# CRSC0002.net
KiCad netlist of a schematic drawn in Altium Designer
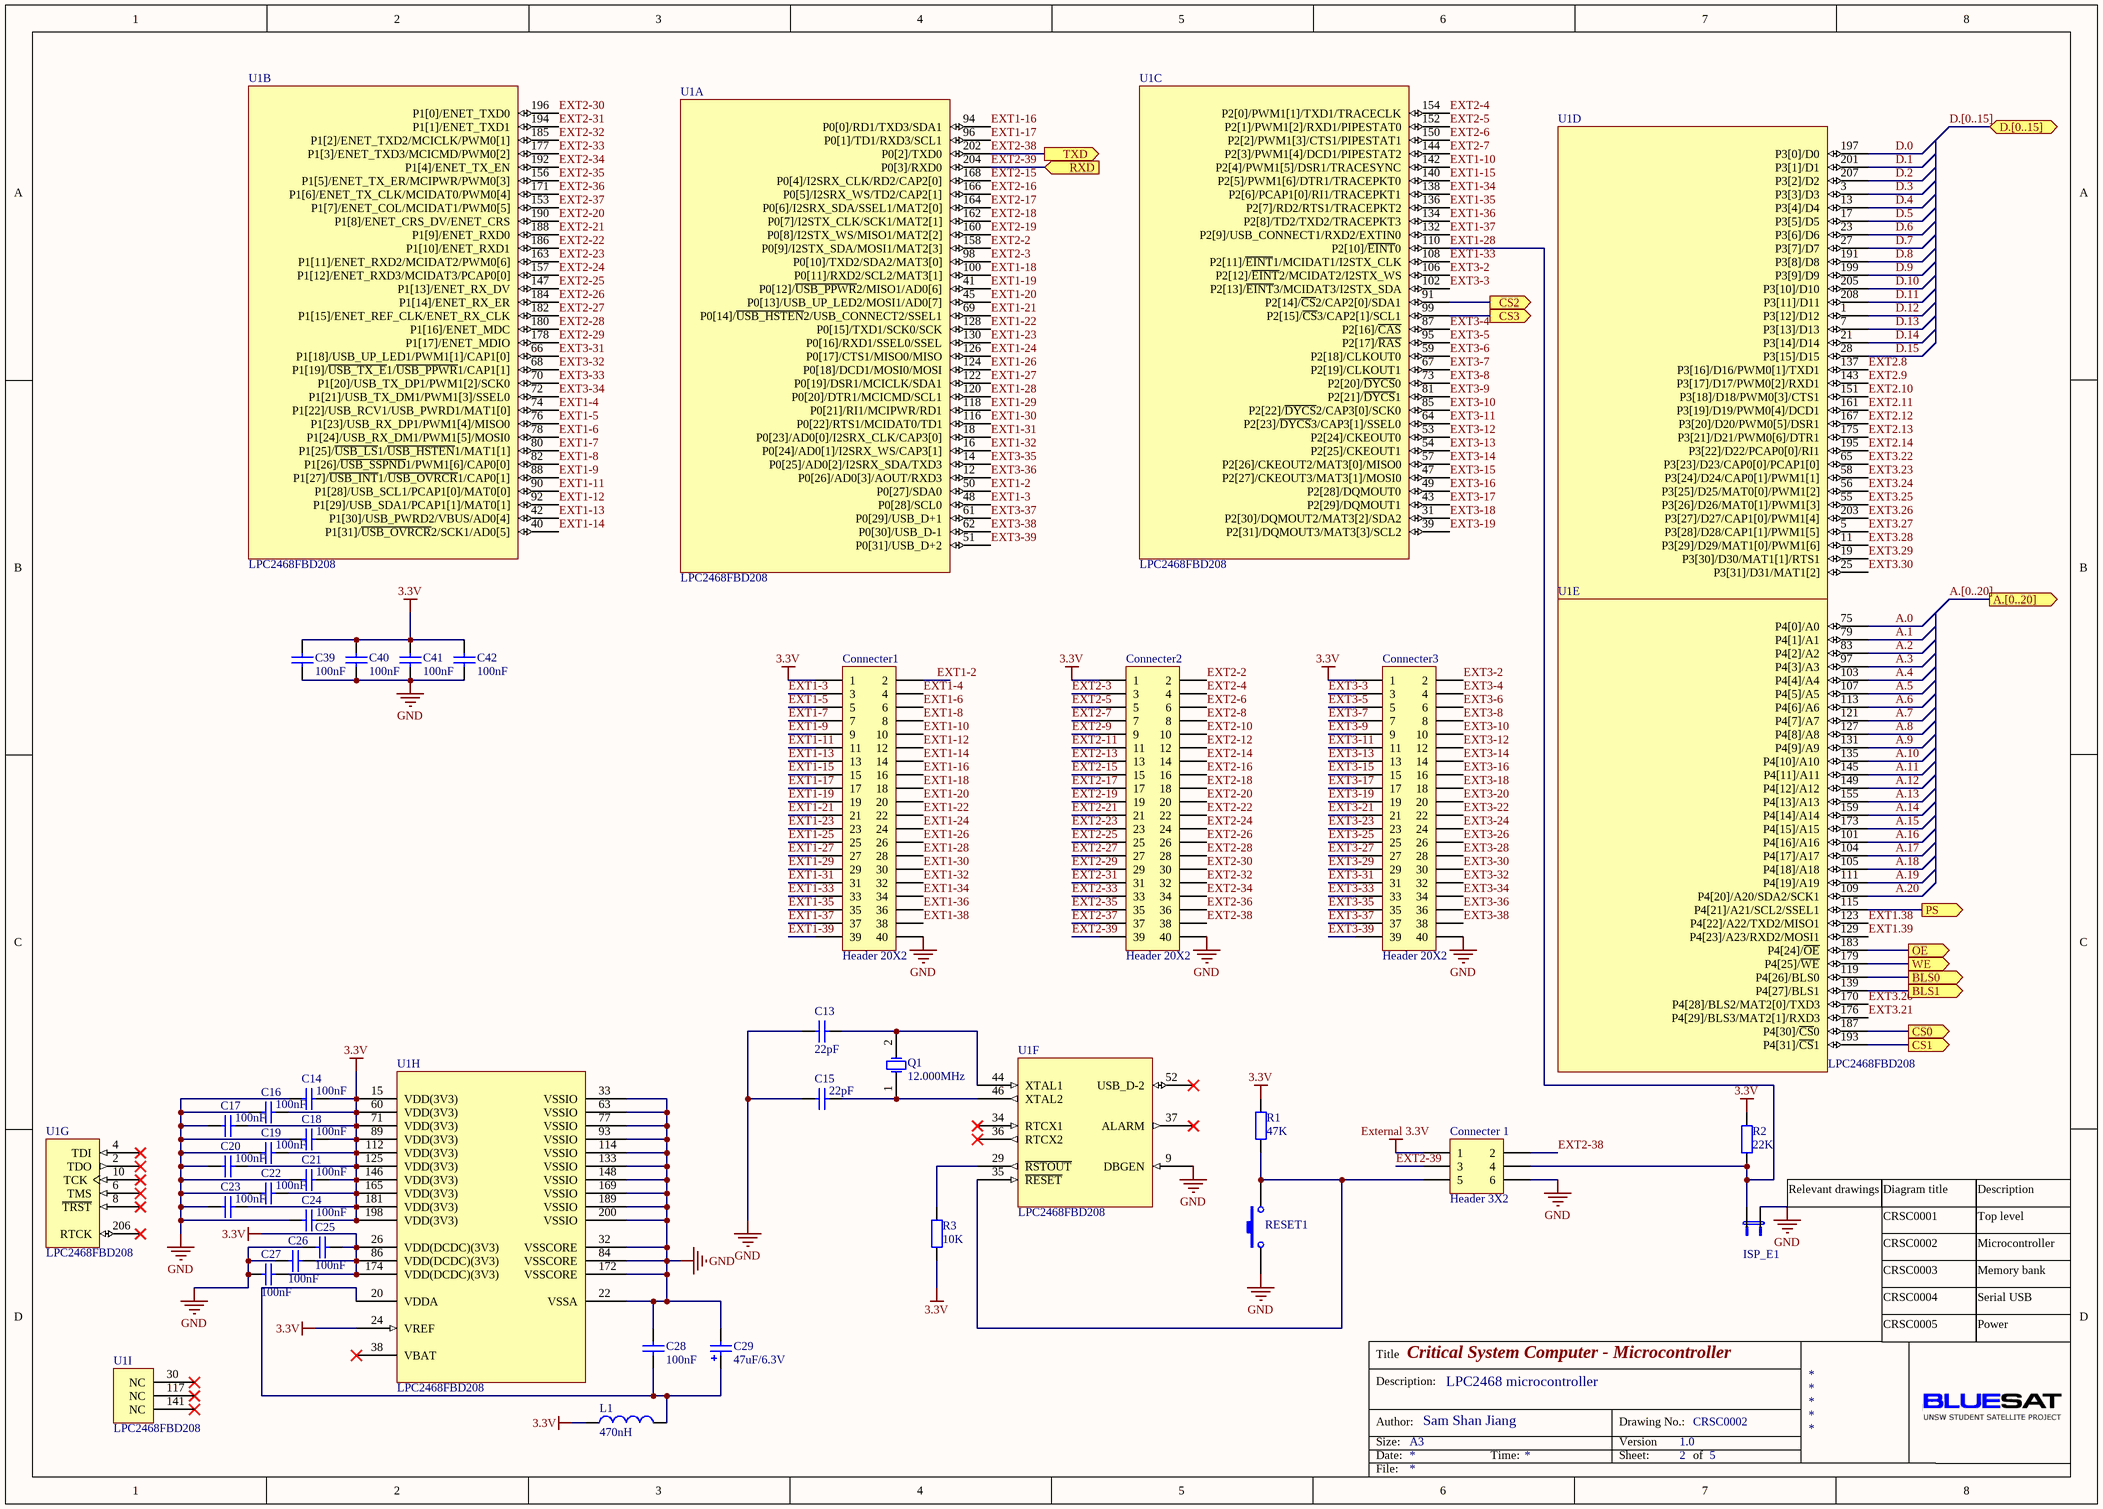
[diagram p0: CRSC0002.SchDoc]

(export (version "E")
  (design (tool "Eeschema 10.0.6"))
  (components
    (comp (ref "C13")
      (value "22pF")
      (footprint "0805")
      (description "Capacitor")
      (fields (field (name "MANUFACTURER") "Generic Components"))
      (libsource (lib "SELF-MADE_1004") (part "Cap"))
    )
    (comp (ref "C14")
      (value "100nF")
      (footprint "0805")
      (description "Capacitor")
      (fields (field (name "MANUFACTURER") "Generic Components"))
      (libsource (lib "SELF-MADE_1004") (part "Cap"))
    )
    (comp (ref "C15")
      (value "22pF")
      (footprint "0805")
      (description "Capacitor")
      (fields (field (name "MANUFACTURER") "Generic Components"))
      (libsource (lib "SELF-MADE_1004") (part "Cap"))
    )
    (comp (ref "C16")
      (value "100nF")
      (footprint "0805")
      (description "Capacitor")
      (fields (field (name "MANUFACTURER") "Generic Components"))
      (libsource (lib "SELF-MADE_1004") (part "Cap"))
    )
    (comp (ref "C17")
      (value "100nF")
      (footprint "0805")
      (description "Capacitor")
      (fields (field (name "MANUFACTURER") "Generic Components"))
      (libsource (lib "SELF-MADE_1004") (part "Cap"))
    )
    (comp (ref "C18")
      (value "100nF")
      (footprint "0805")
      (description "Capacitor")
      (fields (field (name "MANUFACTURER") "Generic Components"))
      (libsource (lib "SELF-MADE_1004") (part "Cap"))
    )
    (comp (ref "C19")
      (value "100nF")
      (footprint "0805")
      (description "Capacitor")
      (fields (field (name "MANUFACTURER") "Generic Components"))
      (libsource (lib "SELF-MADE_1004") (part "Cap"))
    )
    (comp (ref "C20")
      (value "100nF")
      (footprint "0805")
      (description "Capacitor")
      (fields (field (name "MANUFACTURER") "Generic Components"))
      (libsource (lib "SELF-MADE_1004") (part "Cap"))
    )
    (comp (ref "C21")
      (value "100nF")
      (footprint "0805")
      (description "Capacitor")
      (fields (field (name "MANUFACTURER") "Generic Components"))
      (libsource (lib "SELF-MADE_1004") (part "Cap"))
    )
    (comp (ref "C22")
      (value "100nF")
      (footprint "0805")
      (description "Capacitor")
      (fields (field (name "MANUFACTURER") "Generic Components"))
      (libsource (lib "SELF-MADE_1004") (part "Cap"))
    )
    (comp (ref "C23")
      (value "100nF")
      (footprint "0805")
      (description "Capacitor")
      (fields (field (name "MANUFACTURER") "Generic Components"))
      (libsource (lib "SELF-MADE_1004") (part "Cap"))
    )
    (comp (ref "C24")
      (value "100nF")
      (footprint "0805")
      (description "Capacitor")
      (fields (field (name "MANUFACTURER") "Generic Components"))
      (libsource (lib "SELF-MADE_1004") (part "Cap"))
    )
    (comp (ref "C25")
      (value "100nF")
      (footprint "0805")
      (description "Capacitor")
      (fields (field (name "MANUFACTURER") "Generic Components"))
      (libsource (lib "SELF-MADE_1004") (part "Cap"))
    )
    (comp (ref "C26")
      (value "100nF")
      (footprint "0805")
      (description "Capacitor")
      (fields (field (name "MANUFACTURER") "Generic Components"))
      (libsource (lib "SELF-MADE_1004") (part "Cap"))
    )
    (comp (ref "C27")
      (value "100nF")
      (footprint "0805")
      (description "Capacitor")
      (fields (field (name "MANUFACTURER") "Generic Components"))
      (libsource (lib "SELF-MADE_1004") (part "Cap"))
    )
    (comp (ref "C28")
      (value "100nF")
      (footprint "0805")
      (description "Capacitor")
      (fields (field (name "MANUFACTURER") "Generic Components"))
      (libsource (lib "SELF-MADE_1004") (part "Cap"))
    )
    (comp (ref "C29")
      (value "47uF/6.3V")
      (footprint "1206")
      (description "Polarized Capacitor (Surface Mount)")
      (libsource (lib "SELF-MADE_1004") (part "Cap Pol3"))
    )
    (comp (ref "C39")
      (value "100nF")
      (footprint "0805")
      (description "Capacitor")
      (fields (field (name "Comment") "Cap"))
      (libsource (lib "Miscellaneous Devices") (part "Cap"))
    )
    (comp (ref "C40")
      (value "100nF")
      (footprint "0805")
      (description "Capacitor")
      (fields (field (name "Comment") "Cap"))
      (libsource (lib "Miscellaneous Devices") (part "Cap"))
    )
    (comp (ref "C41")
      (value "100nF")
      (footprint "0805")
      (description "Capacitor")
      (fields (field (name "Comment") "Cap"))
      (libsource (lib "Miscellaneous Devices") (part "Cap"))
    )
    (comp (ref "C42")
      (value "100nF")
      (footprint "0805")
      (description "Capacitor")
      (fields (field (name "Comment") "Cap"))
      (libsource (lib "Miscellaneous Devices") (part "Cap"))
    )
    (comp (ref "Connecter 1")
      (value "Header 3X2")
      (footprint "6pins header")
      (description "Header, 5-Pin, Dual row")
      (fields (field (name "MANUFACTURER") "Generic Components"))
      (libsource (lib "SELF-MADE_2905") (part "Header 3X2"))
    )
    (comp (ref "Connecter1")
      (value "Header 20X2")
      (footprint "40pins header")
      (description "Header, 20-Pin, Dual row")
      (fields (field (name "MANUFACTURER") "Generic Components"))
      (libsource (lib "SELF-MADE_2905") (part "Header 20X2"))
    )
    (comp (ref "Connecter2")
      (value "Header 20X2")
      (footprint "40pins header")
      (description "Header, 20-Pin, Dual row")
      (fields (field (name "MANUFACTURER") "Generic Components"))
      (libsource (lib "SELF-MADE_1004") (part "Header 20X2"))
    )
    (comp (ref "Connecter3")
      (value "Header 20X2")
      (footprint "40pins header")
      (description "Header, 20-Pin, Dual row")
      (fields (field (name "MANUFACTURER") "Generic Components"))
      (libsource (lib "SELF-MADE_1004") (part "Header 20X2"))
    )
    (comp (ref "ISP_E1")
      (value "2pins jumper")
      (footprint "JUMPER2pins")
      (libsource (lib "SELF-MADE_2905") (part "2pins jumper"))
    )
    (comp (ref "L1")
      (value "470nH")
      (footprint "0805")
      (description "Inductor")
      (libsource (lib "SELF-MADE_1004") (part "Inductor"))
    )
    (comp (ref "Q1")
      (value "12.000MHz")
      (footprint "HC49/4H_SMX")
      (description "Crystal Oscillator")
      (libsource (lib "SELF-MADE_1004") (part "C.O. 2pins"))
    )
    (comp (ref "R1")
      (value "47K")
      (footprint "0805")
      (description "Resistor")
      (fields (field (name "MANUFACTURER") "Generic Components"))
      (libsource (lib "SELF-MADE_2905") (part "Res2"))
    )
    (comp (ref "R2")
      (value "22K")
      (footprint "0805")
      (description "Resistor")
      (fields (field (name "MANUFACTURER") "Generic Components"))
      (libsource (lib "SELF-MADE_2905") (part "Res2"))
    )
    (comp (ref "R3")
      (value "10K")
      (footprint "0805")
      (description "Resistor")
      (fields (field (name "MANUFACTURER") "Generic Components"))
      (libsource (lib "SELF-MADE_1004") (part "Res2"))
    )
    (comp (ref "RESET1")
      (value "SW-PB")
      (footprint "E-BIP-P4/D10")
      (description "Switch")
      (fields (field (name "MANUFACTURER") "Generic Components"))
      (libsource (lib "SELF-MADE_2905") (part "SW-PB"))
    )
    (comp (ref "U1")
      (value "LPC2468FBD208")
      (footprint "SOT459-1_M")
      (description "ARM7 16/32-Bit Microcontroller, 512KB Flash, 98KB RAM, 208-Lead LQFP")
      (libsource (lib "SELF-MADE_1004") (part "LPC2468FBD208"))
    )
  )
  (nets
    (net (code "1") (name "/A.0") (class "Default")
      (node (ref "U1") (pin "75") (pinfunction "P4[0]/A0_75") (pintype "bidirectional"))
    )
    (net (code "2") (name "/A.1") (class "Default")
      (node (ref "U1") (pin "79") (pinfunction "P4[1]/A1_79") (pintype "bidirectional"))
    )
    (net (code "3") (name "/A.2") (class "Default")
      (node (ref "U1") (pin "83") (pinfunction "P4[2]/A2_83") (pintype "bidirectional"))
    )
    (net (code "4") (name "/A.3") (class "Default")
      (node (ref "U1") (pin "97") (pinfunction "P4[3]/A3_97") (pintype "bidirectional"))
    )
    (net (code "5") (name "/A.4") (class "Default")
      (node (ref "U1") (pin "103") (pinfunction "P4[4]/A4_103") (pintype "bidirectional"))
    )
    (net (code "6") (name "/A.5") (class "Default")
      (node (ref "U1") (pin "107") (pinfunction "P4[5]/A5_107") (pintype "bidirectional"))
    )
    (net (code "7") (name "/A.6") (class "Default")
      (node (ref "U1") (pin "113") (pinfunction "P4[6]/A6_113") (pintype "bidirectional"))
    )
    (net (code "8") (name "/A.7") (class "Default")
      (node (ref "U1") (pin "121") (pinfunction "P4[7]/A7_121") (pintype "bidirectional"))
    )
    (net (code "9") (name "/A.8") (class "Default")
      (node (ref "U1") (pin "127") (pinfunction "P4[8]/A8_127") (pintype "bidirectional"))
    )
    (net (code "10") (name "/A.9") (class "Default")
      (node (ref "U1") (pin "131") (pinfunction "P4[9]/A9_131") (pintype "bidirectional"))
    )
    (net (code "11") (name "/A.10") (class "Default")
      (node (ref "U1") (pin "135") (pinfunction "P4[10]/A10_135") (pintype "bidirectional"))
    )
    (net (code "12") (name "/A.11") (class "Default")
      (node (ref "U1") (pin "145") (pinfunction "P4[11]/A11_145") (pintype "bidirectional"))
    )
    (net (code "13") (name "/A.12") (class "Default")
      (node (ref "U1") (pin "149") (pinfunction "P4[12]/A12_149") (pintype "bidirectional"))
    )
    (net (code "14") (name "/A.13") (class "Default")
      (node (ref "U1") (pin "155") (pinfunction "P4[13]/A13_155") (pintype "bidirectional"))
    )
    (net (code "15") (name "/A.14") (class "Default")
      (node (ref "U1") (pin "159") (pinfunction "P4[14]/A14_159") (pintype "bidirectional"))
    )
    (net (code "16") (name "/A.15") (class "Default")
      (node (ref "U1") (pin "173") (pinfunction "P4[15]/A15_173") (pintype "bidirectional"))
    )
    (net (code "17") (name "/A.16") (class "Default")
      (node (ref "U1") (pin "101") (pinfunction "P4[16]/A16_101") (pintype "bidirectional"))
    )
    (net (code "18") (name "/A.17") (class "Default")
      (node (ref "U1") (pin "104") (pinfunction "P4[17]/A17_104") (pintype "bidirectional"))
    )
    (net (code "19") (name "/A.18") (class "Default")
      (node (ref "U1") (pin "105") (pinfunction "P4[18]/A18_105") (pintype "bidirectional"))
    )
    (net (code "20") (name "/A.19") (class "Default")
      (node (ref "U1") (pin "111") (pinfunction "P4[19]/A19_111") (pintype "bidirectional"))
    )
    (net (code "21") (name "/A.20") (class "Default")
      (node (ref "U1") (pin "109") (pinfunction "P4[20]/A20/SDA2/SCK1_109") (pintype "bidirectional"))
    )
    (net (code "23") (name "/BLS0") (class "Default")
      (node (ref "U1") (pin "119") (pinfunction "P4[26]/BLS0_119") (pintype "bidirectional"))
    )
    (net (code "24") (name "/BLS1") (class "Default")
      (node (ref "U1") (pin "139") (pinfunction "P4[27]/BLS1_139") (pintype "bidirectional"))
    )
    (net (code "25") (name "/CS0") (class "Default")
      (node (ref "U1") (pin "187") (pinfunction "P4[30]/~{CS}0_187") (pintype "bidirectional"))
    )
    (net (code "26") (name "/CS1") (class "Default")
      (node (ref "U1") (pin "193") (pinfunction "P4[31]/~{CS}1_193") (pintype "bidirectional"))
    )
    (net (code "27") (name "/CS2") (class "Default")
      (node (ref "U1") (pin "91") (pinfunction "P2[14]/~{CS}2/CAP2[0]/SDA1_91") (pintype "bidirectional"))
    )
    (net (code "28") (name "/CS3") (class "Default")
      (node (ref "U1") (pin "99") (pinfunction "P2[15]/~{CS}3/CAP2[1]/SCL1_99") (pintype "bidirectional"))
    )
    (net (code "29") (name "/D.0") (class "Default")
      (node (ref "U1") (pin "197") (pinfunction "P3[0]/D0_197") (pintype "bidirectional"))
    )
    (net (code "30") (name "/D.1") (class "Default")
      (node (ref "U1") (pin "201") (pinfunction "P3[1]/D1_201") (pintype "bidirectional"))
    )
    (net (code "31") (name "/D.2") (class "Default")
      (node (ref "U1") (pin "207") (pinfunction "P3[2]/D2_207") (pintype "bidirectional"))
    )
    (net (code "32") (name "/D.3") (class "Default")
      (node (ref "U1") (pin "3") (pinfunction "P3[3]/D3_3") (pintype "bidirectional"))
    )
    (net (code "33") (name "/D.4") (class "Default")
      (node (ref "U1") (pin "13") (pinfunction "P3[4]/D4_13") (pintype "bidirectional"))
    )
    (net (code "34") (name "/D.5") (class "Default")
      (node (ref "U1") (pin "17") (pinfunction "P3[5]/D5_17") (pintype "bidirectional"))
    )
    (net (code "35") (name "/D.6") (class "Default")
      (node (ref "U1") (pin "23") (pinfunction "P3[6]/D6_23") (pintype "bidirectional"))
    )
    (net (code "36") (name "/D.7") (class "Default")
      (node (ref "U1") (pin "27") (pinfunction "P3[7]/D7_27") (pintype "bidirectional"))
    )
    (net (code "37") (name "/D.8") (class "Default")
      (node (ref "U1") (pin "191") (pinfunction "P3[8]/D8_191") (pintype "bidirectional"))
    )
    (net (code "38") (name "/D.9") (class "Default")
      (node (ref "U1") (pin "199") (pinfunction "P3[9]/D9_199") (pintype "bidirectional"))
    )
    (net (code "39") (name "/D.10") (class "Default")
      (node (ref "U1") (pin "205") (pinfunction "P3[10]/D10_205") (pintype "bidirectional"))
    )
    (net (code "40") (name "/D.11") (class "Default")
      (node (ref "U1") (pin "208") (pinfunction "P3[11]/D11_208") (pintype "bidirectional"))
    )
    (net (code "41") (name "/D.12") (class "Default")
      (node (ref "U1") (pin "1") (pinfunction "P3[12]/D12_1") (pintype "bidirectional"))
    )
    (net (code "42") (name "/D.13") (class "Default")
      (node (ref "U1") (pin "7") (pinfunction "P3[13]/D13_7") (pintype "bidirectional"))
    )
    (net (code "43") (name "/D.14") (class "Default")
      (node (ref "U1") (pin "21") (pinfunction "P3[14]/D14_21") (pintype "bidirectional"))
    )
    (net (code "44") (name "/D.15") (class "Default")
      (node (ref "U1") (pin "28") (pinfunction "P3[15]/D15_28") (pintype "bidirectional"))
    )
    (net (code "46") (name "/EXT1-2") (class "Default")
      (node (ref "Connecter1") (pin "2") (pinfunction "2_2") (pintype "passive"))
      (node (ref "U1") (pin "50") (pinfunction "P0[27]/SDA0_50") (pintype "bidirectional"))
    )
    (net (code "47") (name "/EXT1-3") (class "Default")
      (node (ref "Connecter1") (pin "3") (pinfunction "3_3") (pintype "passive"))
      (node (ref "U1") (pin "48") (pinfunction "P0[28]/SCL0_48") (pintype "bidirectional"))
    )
    (net (code "48") (name "/EXT1-4") (class "Default")
      (node (ref "Connecter1") (pin "4") (pinfunction "4_4") (pintype "passive"))
      (node (ref "U1") (pin "74") (pinfunction "P1[22]/USB_RCV1/USB_PWRD1/MAT1[0]_74") (pintype "bidirectional"))
    )
    (net (code "49") (name "/EXT1-5") (class "Default")
      (node (ref "Connecter1") (pin "5") (pinfunction "5_5") (pintype "passive"))
      (node (ref "U1") (pin "76") (pinfunction "P1[23]/USB_RX_DP1/PWM1[4]/MISO0_76") (pintype "bidirectional"))
    )
    (net (code "50") (name "/EXT1-6") (class "Default")
      (node (ref "Connecter1") (pin "6") (pinfunction "6_6") (pintype "passive"))
      (node (ref "U1") (pin "78") (pinfunction "P1[24]/USB_RX_DM1/PWM1[5]/MOSI0_78") (pintype "bidirectional"))
    )
    (net (code "51") (name "/EXT1-7") (class "Default")
      (node (ref "Connecter1") (pin "7") (pinfunction "7_7") (pintype "passive"))
      (node (ref "U1") (pin "80") (pinfunction "P1[25]/~{USB_LS}1/~{USB_HSTEN}1/MAT1[1]_80") (pintype "bidirectional"))
    )
    (net (code "52") (name "/EXT1-8") (class "Default")
      (node (ref "Connecter1") (pin "8") (pinfunction "8_8") (pintype "passive"))
      (node (ref "U1") (pin "82") (pinfunction "P1[26]/~{USB_SSPND}1/PWM1[6]/CAP0[0]_82") (pintype "bidirectional"))
    )
    (net (code "53") (name "/EXT1-9") (class "Default")
      (node (ref "Connecter1") (pin "9") (pinfunction "9_9") (pintype "passive"))
      (node (ref "U1") (pin "88") (pinfunction "P1[27]/~{USB_INT}1/~{USB_OVRCR}1/CAP0[1]_88") (pintype "bidirectional"))
    )
    (net (code "54") (name "/EXT1-10") (class "Default")
      (node (ref "Connecter1") (pin "10") (pinfunction "10_10") (pintype "passive"))
      (node (ref "U1") (pin "142") (pinfunction "P2[4]/PWM1[5]/DSR1/TRACESYNC_142") (pintype "bidirectional"))
    )
    (net (code "55") (name "/EXT1-11") (class "Default")
      (node (ref "Connecter1") (pin "11") (pinfunction "11_11") (pintype "passive"))
      (node (ref "U1") (pin "90") (pinfunction "P1[28]/USB_SCL1/PCAP1[0]/MAT0[0]_90") (pintype "bidirectional"))
    )
    (net (code "56") (name "/EXT1-12") (class "Default")
      (node (ref "Connecter1") (pin "12") (pinfunction "12_12") (pintype "passive"))
      (node (ref "U1") (pin "92") (pinfunction "P1[29]/USB_SDA1/PCAP1[1]/MAT0[1]_92") (pintype "bidirectional"))
    )
    (net (code "57") (name "/EXT1-13") (class "Default")
      (node (ref "Connecter1") (pin "13") (pinfunction "13_13") (pintype "passive"))
      (node (ref "U1") (pin "42") (pinfunction "P1[30]/USB_PWRD2/VBUS/AD0[4]_42") (pintype "bidirectional"))
    )
    (net (code "58") (name "/EXT1-14") (class "Default")
      (node (ref "Connecter1") (pin "14") (pinfunction "14_14") (pintype "passive"))
      (node (ref "U1") (pin "40") (pinfunction "P1[31]/~{USB_OVRCR}2/SCK1/AD0[5]_40") (pintype "bidirectional"))
    )
    (net (code "59") (name "/EXT1-15") (class "Default")
      (node (ref "Connecter1") (pin "15") (pinfunction "15_15") (pintype "passive"))
      (node (ref "U1") (pin "140") (pinfunction "P2[5]/PWM1[6]/DTR1/TRACEPKT0_140") (pintype "bidirectional"))
    )
    (net (code "60") (name "/EXT1-16") (class "Default")
      (node (ref "Connecter1") (pin "16") (pinfunction "16_16") (pintype "passive"))
      (node (ref "U1") (pin "94") (pinfunction "P0[0]/RD1/TXD3/SDA1_94") (pintype "bidirectional"))
    )
    (net (code "61") (name "/EXT1-17") (class "Default")
      (node (ref "Connecter1") (pin "17") (pinfunction "17_17") (pintype "passive"))
      (node (ref "U1") (pin "96") (pinfunction "P0[1]/TD1/RXD3/SCL1_96") (pintype "bidirectional"))
    )
    (net (code "62") (name "/EXT1-18") (class "Default")
      (node (ref "Connecter1") (pin "18") (pinfunction "18_18") (pintype "passive"))
      (node (ref "U1") (pin "100") (pinfunction "P0[11]/RXD2/SCL2/MAT3[1]_100") (pintype "bidirectional"))
    )
    (net (code "63") (name "/EXT1-19") (class "Default")
      (node (ref "Connecter1") (pin "19") (pinfunction "19_19") (pintype "passive"))
      (node (ref "U1") (pin "41") (pinfunction "P0[12]/~{USB_PPWR}2/MISO1/AD0[6]_41") (pintype "bidirectional"))
    )
    (net (code "64") (name "/EXT1-20") (class "Default")
      (node (ref "Connecter1") (pin "20") (pinfunction "20_20") (pintype "passive"))
      (node (ref "U1") (pin "45") (pinfunction "P0[13]/USB_UP_LED2/MOSI1/AD0[7]_45") (pintype "bidirectional"))
    )
    (net (code "65") (name "/EXT1-21") (class "Default")
      (node (ref "Connecter1") (pin "21") (pinfunction "21_21") (pintype "passive"))
      (node (ref "U1") (pin "69") (pinfunction "P0[14]/~{USB_HSTEN}2/USB_CONNECT2/SSEL1_69") (pintype "bidirectional"))
    )
    (net (code "66") (name "/EXT1-22") (class "Default")
      (node (ref "Connecter1") (pin "22") (pinfunction "22_22") (pintype "passive"))
      (node (ref "U1") (pin "128") (pinfunction "P0[15]/TXD1/SCK0/SCK_128") (pintype "bidirectional"))
    )
    (net (code "67") (name "/EXT1-23") (class "Default")
      (node (ref "Connecter1") (pin "23") (pinfunction "23_23") (pintype "passive"))
      (node (ref "U1") (pin "130") (pinfunction "P0[16]/RXD1/SSEL0/SSEL_130") (pintype "bidirectional"))
    )
    (net (code "68") (name "/EXT1-24") (class "Default")
      (node (ref "Connecter1") (pin "24") (pinfunction "24_24") (pintype "passive"))
      (node (ref "U1") (pin "126") (pinfunction "P0[17]/CTS1/MISO0/MISO_126") (pintype "bidirectional"))
    )
    (net (code "69") (name "/EXT1-25") (class "Default")
      (node (ref "Connecter1") (pin "25") (pinfunction "25_25") (pintype "passive"))
    )
    (net (code "70") (name "/EXT1-26") (class "Default")
      (node (ref "Connecter1") (pin "26") (pinfunction "26_26") (pintype "passive"))
      (node (ref "U1") (pin "124") (pinfunction "P0[18]/DCD1/MOSI0/MOSI_124") (pintype "bidirectional"))
    )
    (net (code "71") (name "/EXT1-27") (class "Default")
      (node (ref "Connecter1") (pin "27") (pinfunction "27_27") (pintype "passive"))
      (node (ref "U1") (pin "122") (pinfunction "P0[19]/DSR1/MCICLK/SDA1_122") (pintype "bidirectional"))
    )
    (net (code "72") (name "/EXT1-28") (class "Default")
      (node (ref "Connecter 1") (pin "4") (pinfunction "4_4") (pintype "passive"))
      (node (ref "Connecter1") (pin "28") (pinfunction "28_28") (pintype "passive"))
      (node (ref "ISP_E1") (pin "1") (pinfunction "1_1") (pintype "passive"))
      (node (ref "R2") (pin "1") (pinfunction "1_1") (pintype "passive"))
      (node (ref "U1") (pin "110") (pinfunction "P2[10]/~{EINT}0_110") (pintype "bidirectional"))
      (node (ref "U1") (pin "120") (pinfunction "P0[20]/DTR1/MCICMD/SCL1_120") (pintype "bidirectional"))
    )
    (net (code "73") (name "/EXT1-29") (class "Default")
      (node (ref "Connecter1") (pin "29") (pinfunction "29_29") (pintype "passive"))
      (node (ref "U1") (pin "118") (pinfunction "P0[21]/RI1/MCIPWR/RD1_118") (pintype "bidirectional"))
    )
    (net (code "74") (name "/EXT1-30") (class "Default")
      (node (ref "Connecter1") (pin "30") (pinfunction "30_30") (pintype "passive"))
      (node (ref "U1") (pin "116") (pinfunction "P0[22]/RTS1/MCIDAT0/TD1_116") (pintype "bidirectional"))
    )
    (net (code "75") (name "/EXT1-31") (class "Default")
      (node (ref "Connecter1") (pin "31") (pinfunction "31_31") (pintype "passive"))
      (node (ref "U1") (pin "18") (pinfunction "P0[23]/AD0[0]/I2SRX_CLK/CAP3[0]_18") (pintype "bidirectional"))
    )
    (net (code "76") (name "/EXT1-32") (class "Default")
      (node (ref "Connecter1") (pin "32") (pinfunction "32_32") (pintype "passive"))
      (node (ref "U1") (pin "16") (pinfunction "P0[24]/AD0[1]/I2SRX_WS/CAP3[1]_16") (pintype "bidirectional"))
    )
    (net (code "77") (name "/EXT1-33") (class "Default")
      (node (ref "Connecter1") (pin "33") (pinfunction "33_33") (pintype "passive"))
      (node (ref "U1") (pin "108") (pinfunction "P2[11]/~{EINT}1/MCIDAT1/I2STX_CLK_108") (pintype "bidirectional"))
    )
    (net (code "78") (name "/EXT1-34") (class "Default")
      (node (ref "Connecter1") (pin "34") (pinfunction "34_34") (pintype "passive"))
      (node (ref "U1") (pin "138") (pinfunction "P2[6]/PCAP1[0]/RI1/TRACEPKT1_138") (pintype "bidirectional"))
    )
    (net (code "79") (name "/EXT1-35") (class "Default")
      (node (ref "Connecter1") (pin "35") (pinfunction "35_35") (pintype "passive"))
      (node (ref "U1") (pin "136") (pinfunction "P2[7]/RD2/RTS1/TRACEPKT2_136") (pintype "bidirectional"))
    )
    (net (code "80") (name "/EXT1-36") (class "Default")
      (node (ref "Connecter1") (pin "36") (pinfunction "36_36") (pintype "passive"))
      (node (ref "U1") (pin "134") (pinfunction "P2[8]/TD2/TXD2/TRACEPKT3_134") (pintype "bidirectional"))
    )
    (net (code "81") (name "/EXT1-37") (class "Default")
      (node (ref "Connecter1") (pin "37") (pinfunction "37_37") (pintype "passive"))
      (node (ref "U1") (pin "132") (pinfunction "P2[9]/USB_CONNECT1/RXD2/EXTIN0_132") (pintype "bidirectional"))
    )
    (net (code "82") (name "/EXT1-38") (class "Default")
      (node (ref "Connecter1") (pin "38") (pinfunction "38_38") (pintype "passive"))
    )
    (net (code "83") (name "/EXT1-39") (class "Default")
      (node (ref "Connecter1") (pin "39") (pinfunction "39_39") (pintype "passive"))
    )
    (net (code "84") (name "/EXT1.38") (class "Default")
      (node (ref "U1") (pin "123") (pinfunction "P4[22]/A22/TXD2/MISO1_123") (pintype "bidirectional"))
    )
    (net (code "85") (name "/EXT1.39") (class "Default")
      (node (ref "U1") (pin "129") (pinfunction "P4[23]/A23/RXD2/MOSI1_129") (pintype "bidirectional"))
    )
    (net (code "86") (name "/EXT2-2") (class "Default")
      (node (ref "Connecter2") (pin "2") (pinfunction "2_2") (pintype "passive"))
      (node (ref "U1") (pin "158") (pinfunction "P0[9]/I2STX_SDA/MOSI1/MAT2[3]_158") (pintype "bidirectional"))
    )
    (net (code "87") (name "/EXT2-3") (class "Default")
      (node (ref "Connecter2") (pin "3") (pinfunction "3_3") (pintype "passive"))
      (node (ref "U1") (pin "98") (pinfunction "P0[10]/TXD2/SDA2/MAT3[0]_98") (pintype "bidirectional"))
    )
    (net (code "88") (name "/EXT2-4") (class "Default")
      (node (ref "Connecter2") (pin "4") (pinfunction "4_4") (pintype "passive"))
      (node (ref "U1") (pin "154") (pinfunction "P2[0]/PWM1[1]/TXD1/TRACECLK_154") (pintype "bidirectional"))
    )
    (net (code "89") (name "/EXT2-5") (class "Default")
      (node (ref "Connecter2") (pin "5") (pinfunction "5_5") (pintype "passive"))
      (node (ref "U1") (pin "152") (pinfunction "P2[1]/PWM1[2]/RXD1/PIPESTAT0_152") (pintype "bidirectional"))
    )
    (net (code "90") (name "/EXT2-6") (class "Default")
      (node (ref "Connecter2") (pin "6") (pinfunction "6_6") (pintype "passive"))
      (node (ref "U1") (pin "150") (pinfunction "P2[2]/PWM1[3]/CTS1/PIPESTAT1_150") (pintype "bidirectional"))
    )
    (net (code "91") (name "/EXT2-7") (class "Default")
      (node (ref "Connecter2") (pin "7") (pinfunction "7_7") (pintype "passive"))
      (node (ref "U1") (pin "144") (pinfunction "P2[3]/PWM1[4]/DCD1/PIPESTAT2_144") (pintype "bidirectional"))
    )
    (net (code "92") (name "/EXT2-8") (class "Default")
      (node (ref "Connecter2") (pin "8") (pinfunction "8_8") (pintype "passive"))
    )
    (net (code "93") (name "/EXT2-9") (class "Default")
      (node (ref "Connecter2") (pin "9") (pinfunction "9_9") (pintype "passive"))
    )
    (net (code "94") (name "/EXT2-10") (class "Default")
      (node (ref "Connecter2") (pin "10") (pinfunction "10_10") (pintype "passive"))
    )
    (net (code "95") (name "/EXT2-11") (class "Default")
      (node (ref "Connecter2") (pin "11") (pinfunction "11_11") (pintype "passive"))
    )
    (net (code "96") (name "/EXT2-12") (class "Default")
      (node (ref "Connecter2") (pin "12") (pinfunction "12_12") (pintype "passive"))
    )
    (net (code "97") (name "/EXT2-13") (class "Default")
      (node (ref "Connecter2") (pin "13") (pinfunction "13_13") (pintype "passive"))
    )
    (net (code "98") (name "/EXT2-14") (class "Default")
      (node (ref "Connecter2") (pin "14") (pinfunction "14_14") (pintype "passive"))
    )
    (net (code "99") (name "/EXT2-15") (class "Default")
      (node (ref "Connecter2") (pin "15") (pinfunction "15_15") (pintype "passive"))
      (node (ref "U1") (pin "168") (pinfunction "P0[4]/I2SRX_CLK/RD2/CAP2[0]_168") (pintype "bidirectional"))
    )
    (net (code "100") (name "/EXT2-16") (class "Default")
      (node (ref "Connecter2") (pin "16") (pinfunction "16_16") (pintype "passive"))
      (node (ref "U1") (pin "166") (pinfunction "P0[5]/I2SRX_WS/TD2/CAP2[1]_166") (pintype "bidirectional"))
    )
    (net (code "101") (name "/EXT2-17") (class "Default")
      (node (ref "Connecter2") (pin "17") (pinfunction "17_17") (pintype "passive"))
      (node (ref "U1") (pin "164") (pinfunction "P0[6]/I2SRX_SDA/SSEL1/MAT2[0]_164") (pintype "bidirectional"))
    )
    (net (code "102") (name "/EXT2-18") (class "Default")
      (node (ref "Connecter2") (pin "18") (pinfunction "18_18") (pintype "passive"))
      (node (ref "U1") (pin "162") (pinfunction "P0[7]/I2STX_CLK/SCK1/MAT2[1]_162") (pintype "bidirectional"))
    )
    (net (code "103") (name "/EXT2-19") (class "Default")
      (node (ref "Connecter2") (pin "19") (pinfunction "19_19") (pintype "passive"))
      (node (ref "U1") (pin "160") (pinfunction "P0[8]/I2STX_WS/MISO1/MAT2[2]_160") (pintype "bidirectional"))
    )
    (net (code "104") (name "/EXT2-20") (class "Default")
      (node (ref "Connecter2") (pin "20") (pinfunction "20_20") (pintype "passive"))
      (node (ref "U1") (pin "190") (pinfunction "P1[8]/ENET_CRS_DV/ENET_CRS_190") (pintype "bidirectional"))
    )
    (net (code "105") (name "/EXT2-21") (class "Default")
      (node (ref "Connecter2") (pin "21") (pinfunction "21_21") (pintype "passive"))
      (node (ref "U1") (pin "188") (pinfunction "P1[9]/ENET_RXD0_188") (pintype "bidirectional"))
    )
    (net (code "106") (name "/EXT2-22") (class "Default")
      (node (ref "Connecter2") (pin "22") (pinfunction "22_22") (pintype "passive"))
      (node (ref "U1") (pin "186") (pinfunction "P1[10]/ENET_RXD1_186") (pintype "bidirectional"))
    )
    (net (code "107") (name "/EXT2-23") (class "Default")
      (node (ref "Connecter2") (pin "23") (pinfunction "23_23") (pintype "passive"))
      (node (ref "U1") (pin "163") (pinfunction "P1[11]/ENET_RXD2/MCIDAT2/PWM0[6]_163") (pintype "bidirectional"))
    )
    (net (code "108") (name "/EXT2-24") (class "Default")
      (node (ref "Connecter2") (pin "24") (pinfunction "24_24") (pintype "passive"))
      (node (ref "U1") (pin "157") (pinfunction "P1[12]/ENET_RXD3/MCIDAT3/PCAP0[0]_157") (pintype "bidirectional"))
    )
    (net (code "109") (name "/EXT2-25") (class "Default")
      (node (ref "Connecter2") (pin "25") (pinfunction "25_25") (pintype "passive"))
      (node (ref "U1") (pin "147") (pinfunction "P1[13]/ENET_RX_DV_147") (pintype "bidirectional"))
    )
    (net (code "110") (name "/EXT2-26") (class "Default")
      (node (ref "Connecter2") (pin "26") (pinfunction "26_26") (pintype "passive"))
      (node (ref "U1") (pin "184") (pinfunction "P1[14]/ENET_RX_ER_184") (pintype "bidirectional"))
    )
    (net (code "111") (name "/EXT2-27") (class "Default")
      (node (ref "Connecter2") (pin "27") (pinfunction "27_27") (pintype "passive"))
      (node (ref "U1") (pin "182") (pinfunction "P1[15]/ENET_REF_CLK/ENET_RX_CLK_182") (pintype "bidirectional"))
    )
    (net (code "112") (name "/EXT2-28") (class "Default")
      (node (ref "Connecter2") (pin "28") (pinfunction "28_28") (pintype "passive"))
      (node (ref "U1") (pin "180") (pinfunction "P1[16]/ENET_MDC_180") (pintype "bidirectional"))
    )
    (net (code "113") (name "/EXT2-29") (class "Default")
      (node (ref "Connecter2") (pin "29") (pinfunction "29_29") (pintype "passive"))
      (node (ref "U1") (pin "178") (pinfunction "P1[17]/ENET_MDIO_178") (pintype "bidirectional"))
    )
    (net (code "114") (name "/EXT2-30") (class "Default")
      (node (ref "Connecter2") (pin "30") (pinfunction "30_30") (pintype "passive"))
      (node (ref "U1") (pin "196") (pinfunction "P1[0]/ENET_TXD0_196") (pintype "bidirectional"))
    )
    (net (code "115") (name "/EXT2-31") (class "Default")
      (node (ref "Connecter2") (pin "31") (pinfunction "31_31") (pintype "passive"))
      (node (ref "U1") (pin "194") (pinfunction "P1[1]/ENET_TXD1_194") (pintype "bidirectional"))
    )
    (net (code "116") (name "/EXT2-32") (class "Default")
      (node (ref "Connecter2") (pin "32") (pinfunction "32_32") (pintype "passive"))
      (node (ref "U1") (pin "185") (pinfunction "P1[2]/ENET_TXD2/MCICLK/PWM0[1]_185") (pintype "bidirectional"))
    )
    (net (code "117") (name "/EXT2-33") (class "Default")
      (node (ref "Connecter2") (pin "33") (pinfunction "33_33") (pintype "passive"))
      (node (ref "U1") (pin "177") (pinfunction "P1[3]/ENET_TXD3/MCICMD/PWM0[2]_177") (pintype "bidirectional"))
    )
    (net (code "118") (name "/EXT2-34") (class "Default")
      (node (ref "Connecter2") (pin "34") (pinfunction "34_34") (pintype "passive"))
      (node (ref "U1") (pin "192") (pinfunction "P1[4]/ENET_TX_EN_192") (pintype "bidirectional"))
    )
    (net (code "119") (name "/EXT2-35") (class "Default")
      (node (ref "Connecter2") (pin "35") (pinfunction "35_35") (pintype "passive"))
      (node (ref "U1") (pin "156") (pinfunction "P1[5]/ENET_TX_ER/MCIPWR/PWM0[3]_156") (pintype "bidirectional"))
    )
    (net (code "120") (name "/EXT2-36") (class "Default")
      (node (ref "Connecter2") (pin "36") (pinfunction "36_36") (pintype "passive"))
      (node (ref "U1") (pin "171") (pinfunction "P1[6]/ENET_TX_CLK/MCIDAT0/PWM0[4]_171") (pintype "bidirectional"))
    )
    (net (code "121") (name "/EXT2-37") (class "Default")
      (node (ref "Connecter2") (pin "37") (pinfunction "37_37") (pintype "passive"))
      (node (ref "U1") (pin "153") (pinfunction "P1[7]/ENET_COL/MCIDAT1/PWM0[5]_153") (pintype "bidirectional"))
    )
    (net (code "122") (name "/EXT2-38") (class "Default")
      (node (ref "Connecter 1") (pin "2") (pinfunction "2_2") (pintype "passive"))
      (node (ref "Connecter2") (pin "38") (pinfunction "38_38") (pintype "passive"))
      (node (ref "U1") (pin "202") (pinfunction "P0[2]/TXD0_202") (pintype "bidirectional"))
    )
    (net (code "123") (name "/EXT2-39") (class "Default")
      (node (ref "Connecter 1") (pin "3") (pinfunction "3_3") (pintype "passive"))
      (node (ref "Connecter2") (pin "39") (pinfunction "39_39") (pintype "passive"))
      (node (ref "U1") (pin "204") (pinfunction "P0[3]/RXD0_204") (pintype "bidirectional"))
    )
    (net (code "124") (name "/EXT2.8") (class "Default")
      (node (ref "U1") (pin "137") (pinfunction "P3[16]/D16/PWM0[1]/TXD1_137") (pintype "bidirectional"))
    )
    (net (code "125") (name "/EXT2.9") (class "Default")
      (node (ref "U1") (pin "143") (pinfunction "P3[17]/D17/PWM0[2]/RXD1_143") (pintype "bidirectional"))
    )
    (net (code "126") (name "/EXT2.10") (class "Default")
      (node (ref "U1") (pin "151") (pinfunction "P3[18]/D18/PWM0[3]/CTS1_151") (pintype "bidirectional"))
    )
    (net (code "127") (name "/EXT2.11") (class "Default")
      (node (ref "U1") (pin "161") (pinfunction "P3[19]/D19/PWM0[4]/DCD1_161") (pintype "bidirectional"))
    )
    (net (code "128") (name "/EXT2.12") (class "Default")
      (node (ref "U1") (pin "167") (pinfunction "P3[20]/D20/PWM0[5]/DSR1_167") (pintype "bidirectional"))
    )
    (net (code "129") (name "/EXT2.13") (class "Default")
      (node (ref "U1") (pin "175") (pinfunction "P3[21]/D21/PWM0[6]/DTR1_175") (pintype "bidirectional"))
    )
    (net (code "130") (name "/EXT2.14") (class "Default")
      (node (ref "U1") (pin "195") (pinfunction "P3[22]/D22/PCAP0[0]/RI1_195") (pintype "bidirectional"))
    )
    (net (code "131") (name "/EXT3-2") (class "Default")
      (node (ref "Connecter3") (pin "2") (pinfunction "2_2") (pintype "passive"))
      (node (ref "U1") (pin "106") (pinfunction "P2[12]/~{EINT}2/MCIDAT2/I2STX_WS_106") (pintype "bidirectional"))
    )
    (net (code "132") (name "/EXT3-3") (class "Default")
      (node (ref "Connecter3") (pin "3") (pinfunction "3_3") (pintype "passive"))
      (node (ref "U1") (pin "102") (pinfunction "P2[13]/~{EINT}3/MCIDAT3/I2STX_SDA_102") (pintype "bidirectional"))
    )
    (net (code "133") (name "/EXT3-4") (class "Default")
      (node (ref "Connecter3") (pin "4") (pinfunction "4_4") (pintype "passive"))
      (node (ref "U1") (pin "87") (pinfunction "P2[16]/~{CAS}_87") (pintype "bidirectional"))
    )
    (net (code "134") (name "/EXT3-5") (class "Default")
      (node (ref "Connecter3") (pin "5") (pinfunction "5_5") (pintype "passive"))
      (node (ref "U1") (pin "95") (pinfunction "P2[17]/~{RAS}_95") (pintype "bidirectional"))
    )
    (net (code "135") (name "/EXT3-6") (class "Default")
      (node (ref "Connecter3") (pin "6") (pinfunction "6_6") (pintype "passive"))
      (node (ref "U1") (pin "59") (pinfunction "P2[18]/CLKOUT0_59") (pintype "bidirectional"))
    )
    (net (code "136") (name "/EXT3-7") (class "Default")
      (node (ref "Connecter3") (pin "7") (pinfunction "7_7") (pintype "passive"))
      (node (ref "U1") (pin "67") (pinfunction "P2[19]/CLKOUT1_67") (pintype "bidirectional"))
    )
    (net (code "137") (name "/EXT3-8") (class "Default")
      (node (ref "Connecter3") (pin "8") (pinfunction "8_8") (pintype "passive"))
      (node (ref "U1") (pin "73") (pinfunction "P2[20]/~{DYCS}0_73") (pintype "bidirectional"))
    )
    (net (code "138") (name "/EXT3-9") (class "Default")
      (node (ref "Connecter3") (pin "9") (pinfunction "9_9") (pintype "passive"))
      (node (ref "U1") (pin "81") (pinfunction "P2[21]/~{DYCS}1_81") (pintype "bidirectional"))
    )
    (net (code "139") (name "/EXT3-10") (class "Default")
      (node (ref "Connecter3") (pin "10") (pinfunction "10_10") (pintype "passive"))
      (node (ref "U1") (pin "85") (pinfunction "P2[22]/~{DYCS}2/CAP3[0]/SCK0_85") (pintype "bidirectional"))
    )
    (net (code "140") (name "/EXT3-11") (class "Default")
      (node (ref "Connecter3") (pin "11") (pinfunction "11_11") (pintype "passive"))
      (node (ref "U1") (pin "64") (pinfunction "P2[23]/~{DYCS}3/CAP3[1]/SSEL0_64") (pintype "bidirectional"))
    )
    (net (code "141") (name "/EXT3-12") (class "Default")
      (node (ref "Connecter3") (pin "12") (pinfunction "12_12") (pintype "passive"))
      (node (ref "U1") (pin "53") (pinfunction "P2[24]/CKEOUT0_53") (pintype "bidirectional"))
    )
    (net (code "142") (name "/EXT3-13") (class "Default")
      (node (ref "Connecter3") (pin "13") (pinfunction "13_13") (pintype "passive"))
      (node (ref "U1") (pin "54") (pinfunction "P2[25]/CKEOUT1_54") (pintype "bidirectional"))
    )
    (net (code "143") (name "/EXT3-14") (class "Default")
      (node (ref "Connecter3") (pin "14") (pinfunction "14_14") (pintype "passive"))
      (node (ref "U1") (pin "57") (pinfunction "P2[26]/CKEOUT2/MAT3[0]/MISO0_57") (pintype "bidirectional"))
    )
    (net (code "144") (name "/EXT3-15") (class "Default")
      (node (ref "Connecter3") (pin "15") (pinfunction "15_15") (pintype "passive"))
      (node (ref "U1") (pin "47") (pinfunction "P2[27]/CKEOUT3/MAT3[1]/MOSI0_47") (pintype "bidirectional"))
    )
    (net (code "145") (name "/EXT3-16") (class "Default")
      (node (ref "Connecter3") (pin "16") (pinfunction "16_16") (pintype "passive"))
      (node (ref "U1") (pin "49") (pinfunction "P2[28]/DQMOUT0_49") (pintype "bidirectional"))
    )
    (net (code "146") (name "/EXT3-17") (class "Default")
      (node (ref "Connecter3") (pin "17") (pinfunction "17_17") (pintype "passive"))
      (node (ref "U1") (pin "43") (pinfunction "P2[29]/DQMOUT1_43") (pintype "bidirectional"))
    )
    (net (code "147") (name "/EXT3-18") (class "Default")
      (node (ref "Connecter3") (pin "18") (pinfunction "18_18") (pintype "passive"))
      (node (ref "U1") (pin "31") (pinfunction "P2[30]/DQMOUT2/MAT3[2]/SDA2_31") (pintype "bidirectional"))
    )
    (net (code "148") (name "/EXT3-19") (class "Default")
      (node (ref "Connecter3") (pin "19") (pinfunction "19_19") (pintype "passive"))
      (node (ref "U1") (pin "39") (pinfunction "P2[31]/DQMOUT3/MAT3[3]/SCL2_39") (pintype "bidirectional"))
    )
    (net (code "149") (name "/EXT3-20") (class "Default")
      (node (ref "Connecter3") (pin "20") (pinfunction "20_20") (pintype "passive"))
    )
    (net (code "150") (name "/EXT3-21") (class "Default")
      (node (ref "Connecter3") (pin "21") (pinfunction "21_21") (pintype "passive"))
    )
    (net (code "151") (name "/EXT3-22") (class "Default")
      (node (ref "Connecter3") (pin "22") (pinfunction "22_22") (pintype "passive"))
    )
    (net (code "152") (name "/EXT3-23") (class "Default")
      (node (ref "Connecter3") (pin "23") (pinfunction "23_23") (pintype "passive"))
    )
    (net (code "153") (name "/EXT3-24") (class "Default")
      (node (ref "Connecter3") (pin "24") (pinfunction "24_24") (pintype "passive"))
    )
    (net (code "154") (name "/EXT3-25") (class "Default")
      (node (ref "Connecter3") (pin "25") (pinfunction "25_25") (pintype "passive"))
    )
    (net (code "155") (name "/EXT3-26") (class "Default")
      (node (ref "Connecter3") (pin "26") (pinfunction "26_26") (pintype "passive"))
    )
    (net (code "156") (name "/EXT3-27") (class "Default")
      (node (ref "Connecter3") (pin "27") (pinfunction "27_27") (pintype "passive"))
    )
    (net (code "157") (name "/EXT3-28") (class "Default")
      (node (ref "Connecter3") (pin "28") (pinfunction "28_28") (pintype "passive"))
    )
    (net (code "158") (name "/EXT3-29") (class "Default")
      (node (ref "Connecter3") (pin "29") (pinfunction "29_29") (pintype "passive"))
    )
    (net (code "159") (name "/EXT3-30") (class "Default")
      (node (ref "Connecter3") (pin "30") (pinfunction "30_30") (pintype "passive"))
    )
    (net (code "160") (name "/EXT3-31") (class "Default")
      (node (ref "Connecter3") (pin "31") (pinfunction "31_31") (pintype "passive"))
      (node (ref "U1") (pin "66") (pinfunction "P1[18]/USB_UP_LED1/PWM1[1]/CAP1[0]_66") (pintype "bidirectional"))
    )
    (net (code "161") (name "/EXT3-32") (class "Default")
      (node (ref "Connecter3") (pin "32") (pinfunction "32_32") (pintype "passive"))
      (node (ref "U1") (pin "68") (pinfunction "P1[19]/~{USB_TX_E}1/~{USB_PPWR}1/CAP1[1]_68") (pintype "bidirectional"))
    )
    (net (code "162") (name "/EXT3-33") (class "Default")
      (node (ref "Connecter3") (pin "33") (pinfunction "33_33") (pintype "passive"))
      (node (ref "U1") (pin "70") (pinfunction "P1[20]/USB_TX_DP1/PWM1[2]/SCK0_70") (pintype "bidirectional"))
    )
    (net (code "163") (name "/EXT3-34") (class "Default")
      (node (ref "Connecter3") (pin "34") (pinfunction "34_34") (pintype "passive"))
      (node (ref "U1") (pin "72") (pinfunction "P1[21]/USB_TX_DM1/PWM1[3]/SSEL0_72") (pintype "bidirectional"))
    )
    (net (code "164") (name "/EXT3-35") (class "Default")
      (node (ref "Connecter3") (pin "35") (pinfunction "35_35") (pintype "passive"))
      (node (ref "U1") (pin "14") (pinfunction "P0[25]/AD0[2]/I2SRX_SDA/TXD3_14") (pintype "bidirectional"))
    )
    (net (code "165") (name "/EXT3-36") (class "Default")
      (node (ref "Connecter3") (pin "36") (pinfunction "36_36") (pintype "passive"))
      (node (ref "U1") (pin "12") (pinfunction "P0[26]/AD0[3]/AOUT/RXD3_12") (pintype "bidirectional"))
    )
    (net (code "166") (name "/EXT3-37") (class "Default")
      (node (ref "Connecter3") (pin "37") (pinfunction "37_37") (pintype "passive"))
      (node (ref "U1") (pin "61") (pinfunction "P0[29]/USB_D+1_61") (pintype "bidirectional"))
    )
    (net (code "167") (name "/EXT3-38") (class "Default")
      (node (ref "Connecter3") (pin "38") (pinfunction "38_38") (pintype "passive"))
      (node (ref "U1") (pin "62") (pinfunction "P0[30]/USB_D-1_62") (pintype "bidirectional"))
    )
    (net (code "168") (name "/EXT3-39") (class "Default")
      (node (ref "Connecter3") (pin "39") (pinfunction "39_39") (pintype "passive"))
      (node (ref "U1") (pin "51") (pinfunction "P0[31]/USB_D+2_51") (pintype "bidirectional"))
    )
    (net (code "169") (name "/EXT3.20") (class "Default")
      (node (ref "U1") (pin "170") (pinfunction "P4[28]/BLS2/MAT2[0]/TXD3_170") (pintype "bidirectional"))
    )
    (net (code "170") (name "/EXT3.21") (class "Default")
      (node (ref "U1") (pin "176") (pinfunction "P4[29]/BLS3/MAT2[1]/RXD3_176") (pintype "bidirectional"))
    )
    (net (code "171") (name "/EXT3.22") (class "Default")
      (node (ref "U1") (pin "65") (pinfunction "P3[23]/D23/CAP0[0]/PCAP1[0]_65") (pintype "bidirectional"))
    )
    (net (code "172") (name "/EXT3.23") (class "Default")
      (node (ref "U1") (pin "58") (pinfunction "P3[24]/D24/CAP0[1]/PWM1[1]_58") (pintype "bidirectional"))
    )
    (net (code "173") (name "/EXT3.24") (class "Default")
      (node (ref "U1") (pin "56") (pinfunction "P3[25]/D25/MAT0[0]/PWM1[2]_56") (pintype "bidirectional"))
    )
    (net (code "174") (name "/EXT3.25") (class "Default")
      (node (ref "U1") (pin "55") (pinfunction "P3[26]/D26/MAT0[1]/PWM1[3]_55") (pintype "bidirectional"))
    )
    (net (code "175") (name "/EXT3.26") (class "Default")
      (node (ref "U1") (pin "203") (pinfunction "P3[27]/D27/CAP1[0]/PWM1[4]_203") (pintype "bidirectional"))
    )
    (net (code "176") (name "/EXT3.27") (class "Default")
      (node (ref "U1") (pin "5") (pinfunction "P3[28]/D28/CAP1[1]/PWM1[5]_5") (pintype "bidirectional"))
    )
    (net (code "177") (name "/EXT3.28") (class "Default")
      (node (ref "U1") (pin "11") (pinfunction "P3[29]/D29/MAT1[0]/PWM1[6]_11") (pintype "bidirectional"))
    )
    (net (code "178") (name "/EXT3.29") (class "Default")
      (node (ref "U1") (pin "19") (pinfunction "P3[30]/D30/MAT1[1]/RTS1_19") (pintype "bidirectional"))
    )
    (net (code "179") (name "/EXT3.30") (class "Default")
      (node (ref "U1") (pin "25") (pinfunction "P3[31]/D31/MAT1[2]_25") (pintype "bidirectional"))
    )
    (net (code "180") (name "/OE") (class "Default")
      (node (ref "U1") (pin "183") (pinfunction "P4[24]/~{OE}_183") (pintype "bidirectional"))
    )
    (net (code "181") (name "/PS") (class "Default")
      (node (ref "U1") (pin "115") (pinfunction "P4[21]/A21/SCL2/SSEL1_115") (pintype "bidirectional"))
    )
    (net (code "182") (name "/WE") (class "Default")
      (node (ref "U1") (pin "179") (pinfunction "P4[25]/~{WE}_179") (pintype "bidirectional"))
    )
    (net (code "183") (name "3.3V") (class "Default")
      (node (ref "C14") (pin "2") (pinfunction "2_2") (pintype "passive"))
      (node (ref "C16") (pin "2") (pinfunction "2_2") (pintype "passive"))
      (node (ref "C17") (pin "2") (pinfunction "2_2") (pintype "passive"))
      (node (ref "C18") (pin "2") (pinfunction "2_2") (pintype "passive"))
      (node (ref "C19") (pin "2") (pinfunction "2_2") (pintype "passive"))
      (node (ref "C20") (pin "2") (pinfunction "2_2") (pintype "passive"))
      (node (ref "C21") (pin "2") (pinfunction "2_2") (pintype "passive"))
      (node (ref "C22") (pin "2") (pinfunction "2_2") (pintype "passive"))
      (node (ref "C23") (pin "2") (pinfunction "2_2") (pintype "passive"))
      (node (ref "C24") (pin "2") (pinfunction "2_2") (pintype "passive"))
      (node (ref "C25") (pin "2") (pinfunction "2_2") (pintype "passive"))
      (node (ref "C26") (pin "2") (pinfunction "2_2") (pintype "passive"))
      (node (ref "C27") (pin "2") (pinfunction "2_2") (pintype "passive"))
      (node (ref "C39") (pin "2") (pinfunction "2_2") (pintype "passive"))
      (node (ref "C40") (pin "2") (pinfunction "2_2") (pintype "passive"))
      (node (ref "C41") (pin "2") (pinfunction "2_2") (pintype "passive"))
      (node (ref "C42") (pin "2") (pinfunction "2_2") (pintype "passive"))
      (node (ref "Connecter1") (pin "1") (pinfunction "1_1") (pintype "passive"))
      (node (ref "Connecter2") (pin "1") (pinfunction "1_1") (pintype "passive"))
      (node (ref "Connecter3") (pin "1") (pinfunction "1_1") (pintype "passive"))
      (node (ref "L1") (pin "1") (pinfunction "1_1") (pintype "passive"))
      (node (ref "R1") (pin "2") (pinfunction "2_2") (pintype "passive"))
      (node (ref "R2") (pin "2") (pinfunction "2_2") (pintype "passive"))
      (node (ref "R3") (pin "2") (pinfunction "2_2") (pintype "passive"))
      (node (ref "U1") (pin "112") (pinfunction "VDD(3V3)_112") (pintype "power_in"))
      (node (ref "U1") (pin "125") (pinfunction "VDD(3V3)_125") (pintype "power_in"))
      (node (ref "U1") (pin "146") (pinfunction "VDD(3V3)_146") (pintype "power_in"))
      (node (ref "U1") (pin "15") (pinfunction "VDD(3V3)_15") (pintype "power_in"))
      (node (ref "U1") (pin "165") (pinfunction "VDD(3V3)_165") (pintype "power_in"))
      (node (ref "U1") (pin "174") (pinfunction "VDD(DCDC)(3V3)_174") (pintype "power_in"))
      (node (ref "U1") (pin "181") (pinfunction "VDD(3V3)_181") (pintype "power_in"))
      (node (ref "U1") (pin "198") (pinfunction "VDD(3V3)_198") (pintype "power_in"))
      (node (ref "U1") (pin "24") (pinfunction "VREF_24") (pintype "input"))
      (node (ref "U1") (pin "26") (pinfunction "VDD(DCDC)(3V3)_26") (pintype "power_in"))
      (node (ref "U1") (pin "60") (pinfunction "VDD(3V3)_60") (pintype "power_in"))
      (node (ref "U1") (pin "71") (pinfunction "VDD(3V3)_71") (pintype "power_in"))
      (node (ref "U1") (pin "86") (pinfunction "VDD(DCDC)(3V3)_86") (pintype "power_in"))
      (node (ref "U1") (pin "89") (pinfunction "VDD(3V3)_89") (pintype "power_in"))
    )
    (net (code "184") (name "External 3.3V") (class "Default")
      (node (ref "Connecter 1") (pin "1") (pinfunction "1_1") (pintype "passive"))
    )
    (net (code "185") (name "GND") (class "Default")
      (node (ref "C13") (pin "2") (pinfunction "2_2") (pintype "passive"))
      (node (ref "C14") (pin "1") (pinfunction "1_1") (pintype "passive"))
      (node (ref "C15") (pin "2") (pinfunction "2_2") (pintype "passive"))
      (node (ref "C16") (pin "1") (pinfunction "1_1") (pintype "passive"))
      (node (ref "C17") (pin "1") (pinfunction "1_1") (pintype "passive"))
      (node (ref "C18") (pin "1") (pinfunction "1_1") (pintype "passive"))
      (node (ref "C19") (pin "1") (pinfunction "1_1") (pintype "passive"))
      (node (ref "C20") (pin "1") (pinfunction "1_1") (pintype "passive"))
      (node (ref "C21") (pin "1") (pinfunction "1_1") (pintype "passive"))
      (node (ref "C22") (pin "1") (pinfunction "1_1") (pintype "passive"))
      (node (ref "C23") (pin "1") (pinfunction "1_1") (pintype "passive"))
      (node (ref "C24") (pin "1") (pinfunction "1_1") (pintype "passive"))
      (node (ref "C25") (pin "1") (pinfunction "1_1") (pintype "passive"))
      (node (ref "C26") (pin "1") (pinfunction "1_1") (pintype "passive"))
      (node (ref "C27") (pin "1") (pinfunction "1_1") (pintype "passive"))
      (node (ref "C28") (pin "2") (pinfunction "2_2") (pintype "passive"))
      (node (ref "C29") (pin "2") (pinfunction "2_2") (pintype "passive"))
      (node (ref "C39") (pin "1") (pinfunction "1_1") (pintype "passive"))
      (node (ref "C40") (pin "1") (pinfunction "1_1") (pintype "passive"))
      (node (ref "C41") (pin "1") (pinfunction "1_1") (pintype "passive"))
      (node (ref "C42") (pin "1") (pinfunction "1_1") (pintype "passive"))
      (node (ref "Connecter 1") (pin "6") (pinfunction "6_6") (pintype "passive"))
      (node (ref "Connecter1") (pin "40") (pinfunction "40_40") (pintype "passive"))
      (node (ref "Connecter2") (pin "40") (pinfunction "40_40") (pintype "passive"))
      (node (ref "Connecter3") (pin "40") (pinfunction "40_40") (pintype "passive"))
      (node (ref "ISP_E1") (pin "2") (pinfunction "2_2") (pintype "passive"))
      (node (ref "RESET1") (pin "1") (pinfunction "1_1") (pintype "passive"))
      (node (ref "U1") (pin "114") (pinfunction "VSSIO_114") (pintype "power_in"))
      (node (ref "U1") (pin "133") (pinfunction "VSSIO_133") (pintype "power_in"))
      (node (ref "U1") (pin "148") (pinfunction "VSSIO_148") (pintype "power_in"))
      (node (ref "U1") (pin "169") (pinfunction "VSSIO_169") (pintype "power_in"))
      (node (ref "U1") (pin "172") (pinfunction "VSSCORE_172") (pintype "power_in"))
      (node (ref "U1") (pin "189") (pinfunction "VSSIO_189") (pintype "power_in"))
      (node (ref "U1") (pin "200") (pinfunction "VSSIO_200") (pintype "power_in"))
      (node (ref "U1") (pin "22") (pinfunction "VSSA_22") (pintype "power_in"))
      (node (ref "U1") (pin "32") (pinfunction "VSSCORE_32") (pintype "power_in"))
      (node (ref "U1") (pin "33") (pinfunction "VSSIO_33") (pintype "power_in"))
      (node (ref "U1") (pin "63") (pinfunction "VSSIO_63") (pintype "power_in"))
      (node (ref "U1") (pin "77") (pinfunction "VSSIO_77") (pintype "power_in"))
      (node (ref "U1") (pin "84") (pinfunction "VSSCORE_84") (pintype "power_in"))
      (node (ref "U1") (pin "9") (pinfunction "DBGEN_9") (pintype "input"))
      (node (ref "U1") (pin "93") (pinfunction "VSSIO_93") (pintype "power_in"))
    )
    (net (code "186") (name "Net-(Q1-OSC1)") (class "Default")
      (node (ref "C15") (pin "1") (pinfunction "1_1") (pintype "passive"))
      (node (ref "Q1") (pin "1") (pinfunction "OSC1_1") (pintype "passive"))
      (node (ref "U1") (pin "46") (pinfunction "XTAL2_46") (pintype "output"))
    )
    (net (code "187") (name "Net-(Q1-OSC2)") (class "Default")
      (node (ref "C13") (pin "1") (pinfunction "1_1") (pintype "passive"))
      (node (ref "Q1") (pin "2") (pinfunction "OSC2_2") (pintype "passive"))
      (node (ref "U1") (pin "44") (pinfunction "XTAL1_44") (pintype "input"))
    )
    (net (code "188") (name "Net-(U1F-~{RESET})") (class "Default")
      (node (ref "Connecter 1") (pin "5") (pinfunction "5_5") (pintype "passive"))
      (node (ref "R1") (pin "1") (pinfunction "1_1") (pintype "passive"))
      (node (ref "RESET1") (pin "2") (pinfunction "2_2") (pintype "passive"))
      (node (ref "U1") (pin "35") (pinfunction "~{RESET}_35") (pintype "input"))
    )
    (net (code "189") (name "Net-(U1F-~{RSTOUT})") (class "Default")
      (node (ref "R3") (pin "1") (pinfunction "1_1") (pintype "passive"))
      (node (ref "U1") (pin "29") (pinfunction "~{RSTOUT}_29") (pintype "output"))
    )
    (net (code "190") (name "Net-(U1H-VDDA)") (class "Default")
      (node (ref "C28") (pin "1") (pinfunction "1_1") (pintype "passive"))
      (node (ref "C29") (pin "1") (pinfunction "1_1") (pintype "passive"))
      (node (ref "L1") (pin "2") (pinfunction "2_2") (pintype "passive"))
      (node (ref "U1") (pin "20") (pinfunction "VDDA_20") (pintype "power_in"))
    )
    (net (code "191") (name "unconnected-(U1F-ALARM-Pad37)") (class "Default")
      (node (ref "U1") (pin "37") (pinfunction "ALARM_37") (pintype "output+no_connect"))
    )
    (net (code "192") (name "unconnected-(U1F-RTCX1-Pad34)") (class "Default")
      (node (ref "U1") (pin "34") (pinfunction "RTCX1_34") (pintype "input+no_connect"))
    )
    (net (code "193") (name "unconnected-(U1F-RTCX2-Pad36)") (class "Default")
      (node (ref "U1") (pin "36") (pinfunction "RTCX2_36") (pintype "output+no_connect"))
    )
    (net (code "194") (name "unconnected-(U1F-USB_D-2-Pad52)") (class "Default")
      (node (ref "U1") (pin "52") (pinfunction "USB_D-2_52") (pintype "bidirectional+no_connect"))
    )
    (net (code "195") (name "unconnected-(U1G-RTCK-Pad206)") (class "Default")
      (node (ref "U1") (pin "206") (pinfunction "RTCK_206") (pintype "bidirectional+no_connect"))
    )
    (net (code "196") (name "unconnected-(U1G-TCK-Pad10)") (class "Default")
      (node (ref "U1") (pin "10") (pinfunction "TCK_10") (pintype "input+no_connect"))
    )
    (net (code "197") (name "unconnected-(U1G-TDI-Pad4)") (class "Default")
      (node (ref "U1") (pin "4") (pinfunction "TDI_4") (pintype "input+no_connect"))
    )
    (net (code "198") (name "unconnected-(U1G-TDO-Pad2)") (class "Default")
      (node (ref "U1") (pin "2") (pinfunction "TDO_2") (pintype "output+no_connect"))
    )
    (net (code "199") (name "unconnected-(U1G-TMS-Pad6)") (class "Default")
      (node (ref "U1") (pin "6") (pinfunction "TMS_6") (pintype "input+no_connect"))
    )
    (net (code "200") (name "unconnected-(U1G-~{TRST}-Pad8)") (class "Default")
      (node (ref "U1") (pin "8") (pinfunction "~{TRST}_8") (pintype "input+no_connect"))
    )
    (net (code "201") (name "unconnected-(U1H-VBAT-Pad38)") (class "Default")
      (node (ref "U1") (pin "38") (pinfunction "VBAT_38") (pintype "power_in+no_connect"))
    )
    (net (code "202") (name "unconnected-(U1I-NC-Pad30)") (class "Default")
      (node (ref "U1") (pin "30") (pinfunction "NC_30") (pintype "passive+no_connect"))
    )
    (net (code "203") (name "unconnected-(U1I-NC-Pad117)") (class "Default")
      (node (ref "U1") (pin "117") (pinfunction "NC_117") (pintype "passive+no_connect"))
    )
    (net (code "204") (name "unconnected-(U1I-NC-Pad141)") (class "Default")
      (node (ref "U1") (pin "141") (pinfunction "NC_141") (pintype "passive+no_connect"))
    )
  )
)
